# EndingsACMixOutput.net
KiCad netlist of a schematic drawn in EAGLE
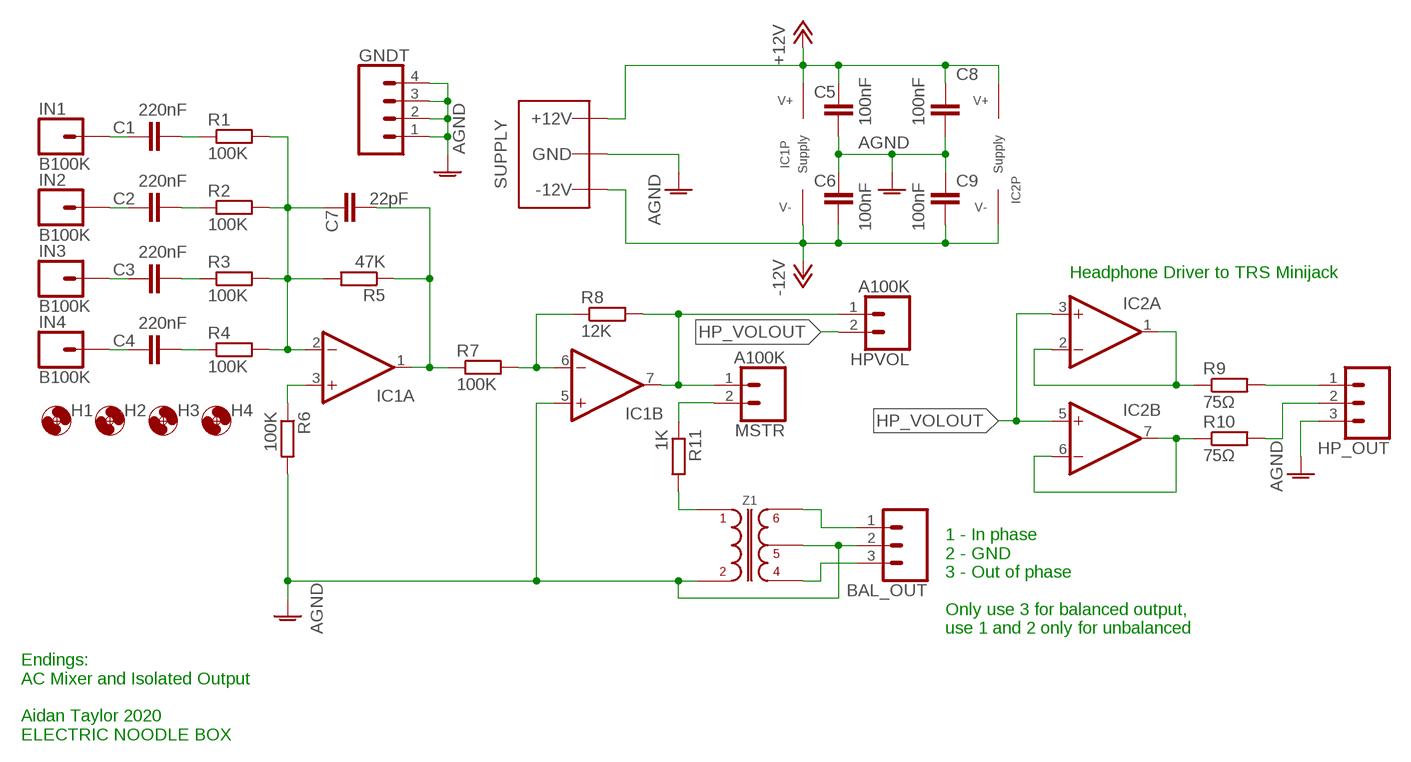
[diagram p0: schematic, sheet 1]

(export (version "E")
  (design (tool "Eeschema 10.0.6"))
  (components
    (comp (ref "BAL_OUT")
      (value "3XWIREPAD")
      (footprint "eagle-import:1X03")
      (libsource (lib "eagle-import") (part "3XWIREPAD"))
    )
    (comp (ref "C1")
      (value "220nF")
      (footprint "eagle-import:C050-025X075")
      (libsource (lib "eagle-import") (part "C-EU050-025X075"))
    )
    (comp (ref "C2")
      (value "220nF")
      (footprint "eagle-import:C050-025X075")
      (libsource (lib "eagle-import") (part "C-EU050-025X075"))
    )
    (comp (ref "C3")
      (value "220nF")
      (footprint "eagle-import:C050-025X075")
      (libsource (lib "eagle-import") (part "C-EU050-025X075"))
    )
    (comp (ref "C4")
      (value "220nF")
      (footprint "eagle-import:C050-025X075")
      (libsource (lib "eagle-import") (part "C-EU050-025X075"))
    )
    (comp (ref "C5")
      (value "100nF")
      (footprint "eagle-import:C050-025X075")
      (libsource (lib "eagle-import") (part "C-EU050-025X075"))
    )
    (comp (ref "C6")
      (value "100nF")
      (footprint "eagle-import:C050-025X075")
      (libsource (lib "eagle-import") (part "C-EU050-025X075"))
    )
    (comp (ref "C7")
      (value "22pF")
      (footprint "eagle-import:C050-025X075")
      (libsource (lib "eagle-import") (part "C-EU050-025X075"))
    )
    (comp (ref "C8")
      (value "100nF")
      (footprint "eagle-import:C050-025X075")
      (libsource (lib "eagle-import") (part "C-EU050-025X075"))
    )
    (comp (ref "C9")
      (value "100nF")
      (footprint "eagle-import:C050-025X075")
      (libsource (lib "eagle-import") (part "C-EU050-025X075"))
    )
    (comp (ref "GNDT")
      (value "4XWIREPAD")
      (footprint "eagle-import:1X04")
      (libsource (lib "eagle-import") (part "4XWIREPAD"))
    )
    (comp (ref "H1")
      (value "MOUNT-HOLE3.2")
      (footprint "eagle-import:3,2")
      (libsource (lib "eagle-import") (part "MOUNT-HOLE3.2"))
    )
    (comp (ref "H2")
      (value "MOUNT-HOLE3.2")
      (footprint "eagle-import:3,2")
      (libsource (lib "eagle-import") (part "MOUNT-HOLE3.2"))
    )
    (comp (ref "H3")
      (value "MOUNT-HOLE3.2")
      (footprint "eagle-import:3,2")
      (libsource (lib "eagle-import") (part "MOUNT-HOLE3.2"))
    )
    (comp (ref "H4")
      (value "MOUNT-HOLE3.2")
      (footprint "eagle-import:3,2")
      (libsource (lib "eagle-import") (part "MOUNT-HOLE3.2"))
    )
    (comp (ref "HPVOL")
      (value "A100K")
      (footprint "eagle-import:1X02")
      (libsource (lib "eagle-import") (part "2XWIREPAD"))
    )
    (comp (ref "HP_OUT")
      (value "3XWIREPAD")
      (footprint "eagle-import:1X03")
      (libsource (lib "eagle-import") (part "3XWIREPAD"))
    )
    (comp (ref "IC1")
      (value "TL0X2DIL")
      (footprint "eagle-import:DIL08")
      (libsource (lib "eagle-import") (part "TL0X2DIL"))
    )
    (comp (ref "IC2")
      (value "TL0X2DIL")
      (footprint "eagle-import:DIL08")
      (libsource (lib "eagle-import") (part "TL0X2DIL"))
    )
    (comp (ref "IN1")
      (value "B100K")
      (footprint "eagle-import:1X01")
      (libsource (lib "eagle-import") (part "1XWIREPAD"))
    )
    (comp (ref "IN2")
      (value "B100K")
      (footprint "eagle-import:1X01")
      (libsource (lib "eagle-import") (part "1XWIREPAD"))
    )
    (comp (ref "IN3")
      (value "B100K")
      (footprint "eagle-import:1X01")
      (libsource (lib "eagle-import") (part "1XWIREPAD"))
    )
    (comp (ref "IN4")
      (value "B100K")
      (footprint "eagle-import:1X01")
      (libsource (lib "eagle-import") (part "1XWIREPAD"))
    )
    (comp (ref "MSTR")
      (value "A100K")
      (footprint "eagle-import:1X02")
      (libsource (lib "eagle-import") (part "2XWIREPAD"))
    )
    (comp (ref "R1")
      (value "100K")
      (footprint "eagle-import:0207_10")
      (libsource (lib "eagle-import") (part "R-EU_0207/10"))
    )
    (comp (ref "R2")
      (value "100K")
      (footprint "eagle-import:0207_10")
      (libsource (lib "eagle-import") (part "R-EU_0207/10"))
    )
    (comp (ref "R3")
      (value "100K")
      (footprint "eagle-import:0207_10")
      (libsource (lib "eagle-import") (part "R-EU_0207/10"))
    )
    (comp (ref "R4")
      (value "100K")
      (footprint "eagle-import:0207_10")
      (libsource (lib "eagle-import") (part "R-EU_0207/10"))
    )
    (comp (ref "R5")
      (value "47K")
      (footprint "eagle-import:0207_10")
      (libsource (lib "eagle-import") (part "R-EU_0207/10"))
    )
    (comp (ref "R6")
      (value "100K")
      (footprint "eagle-import:0207_10")
      (libsource (lib "eagle-import") (part "R-EU_0207/10"))
    )
    (comp (ref "R7")
      (value "100K")
      (footprint "eagle-import:0207_10")
      (libsource (lib "eagle-import") (part "R-EU_0207/10"))
    )
    (comp (ref "R8")
      (value "12K")
      (footprint "eagle-import:0207_10")
      (libsource (lib "eagle-import") (part "R-EU_0207/10"))
    )
    (comp (ref "R9")
      (value "75Ω")
      (footprint "eagle-import:0207_10")
      (libsource (lib "eagle-import") (part "R-EU_0207/10"))
    )
    (comp (ref "R10")
      (value "75Ω")
      (footprint "eagle-import:0207_10")
      (libsource (lib "eagle-import") (part "R-EU_0207/10"))
    )
    (comp (ref "R11")
      (value "1K")
      (footprint "eagle-import:0207_10")
      (libsource (lib "eagle-import") (part "R-EU_0207/10"))
    )
    (comp (ref "WP1")
      (value "COMBO_SUPPLY_HEADER")
      (footprint "eagle-import:COMBINED_POWER")
      (libsource (lib "eagle-import") (part "COMBO_SUPPLY_HEADER"))
    )
    (comp (ref "Z1")
      (value "Z1604_AUDIO_TRANSFORMER")
      (footprint "eagle-import:Z1604_TRANSFORMER")
      (libsource (lib "eagle-import") (part "Z1604_AUDIO_TRANSFORMER"))
    )
  )
  (nets
    (net (code "1") (name "+12V") (class "Default")
      (node (ref "C5") (pin "1") (pinfunction "1_1") (pintype "passive"))
      (node (ref "C8") (pin "1") (pinfunction "1_1") (pintype "passive"))
      (node (ref "IC1") (pin "8") (pinfunction "V+_8") (pintype "bidirectional"))
      (node (ref "IC2") (pin "8") (pinfunction "V+_8") (pintype "bidirectional"))
      (node (ref "WP1") (pin "V+1") (pinfunction "V++_V+1") (pintype "power_in"))
      (node (ref "WP1") (pin "V+2") (pinfunction "V++_V+2") (pintype "power_in"))
      (node (ref "WP1") (pin "V+3") (pinfunction "V++_V+3") (pintype "power_in"))
    )
    (net (code "2") (name "-12V") (class "Default")
      (node (ref "C6") (pin "2") (pinfunction "2_2") (pintype "passive"))
      (node (ref "C9") (pin "2") (pinfunction "2_2") (pintype "passive"))
      (node (ref "IC1") (pin "4") (pinfunction "V-_4") (pintype "bidirectional"))
      (node (ref "IC2") (pin "4") (pinfunction "V-_4") (pintype "bidirectional"))
      (node (ref "WP1") (pin "V-1") (pinfunction "V--_V-1") (pintype "power_in"))
      (node (ref "WP1") (pin "V-2") (pinfunction "V--_V-2") (pintype "power_in"))
      (node (ref "WP1") (pin "V-3") (pinfunction "V--_V-3") (pintype "power_in"))
    )
    (net (code "3") (name "AGND") (class "Default")
      (node (ref "BAL_OUT") (pin "2") (pinfunction "2_2") (pintype "passive"))
      (node (ref "C5") (pin "2") (pinfunction "2_2") (pintype "passive"))
      (node (ref "C6") (pin "1") (pinfunction "1_1") (pintype "passive"))
      (node (ref "C8") (pin "2") (pinfunction "2_2") (pintype "passive"))
      (node (ref "C9") (pin "1") (pinfunction "1_1") (pintype "passive"))
      (node (ref "GNDT") (pin "1") (pinfunction "1_1") (pintype "passive"))
      (node (ref "GNDT") (pin "2") (pinfunction "2_2") (pintype "passive"))
      (node (ref "GNDT") (pin "3") (pinfunction "3_3") (pintype "passive"))
      (node (ref "GNDT") (pin "4") (pinfunction "4_4") (pintype "passive"))
      (node (ref "HP_OUT") (pin "3") (pinfunction "3_3") (pintype "passive"))
      (node (ref "IC1") (pin "5") (pinfunction "+IN_5") (pintype "input"))
      (node (ref "R6") (pin "2") (pinfunction "2_2") (pintype "passive"))
      (node (ref "WP1") (pin "GND1") (pinfunction "AGND_GND1") (pintype "power_in"))
      (node (ref "WP1") (pin "GND2") (pinfunction "AGND_GND2") (pintype "power_in"))
      (node (ref "WP1") (pin "GND3") (pinfunction "AGND_GND3") (pintype "power_in"))
      (node (ref "WP1") (pin "GND4") (pinfunction "AGND_GND4") (pintype "power_in"))
      (node (ref "WP1") (pin "GND5") (pinfunction "AGND_GND5") (pintype "power_in"))
      (node (ref "WP1") (pin "GND6") (pinfunction "AGND_GND6") (pintype "power_in"))
      (node (ref "WP1") (pin "GND7") (pinfunction "AGND_GND7") (pintype "power_in"))
      (node (ref "WP1") (pin "GND8") (pinfunction "AGND_GND8") (pintype "power_in"))
      (node (ref "Z1") (pin "T3") (pinfunction "3_T3") (pintype "bidirectional"))
      (node (ref "Z1") (pin "T5") (pinfunction "5_T5") (pintype "bidirectional"))
    )
    (net (code "4") (name "HP_VOLOUT") (class "Default")
      (node (ref "HPVOL") (pin "2") (pinfunction "2_2") (pintype "passive"))
      (node (ref "IC2") (pin "3") (pinfunction "+IN_3") (pintype "input"))
      (node (ref "IC2") (pin "5") (pinfunction "+IN_5") (pintype "input"))
    )
    (net (code "5") (name "Net-(C1-Pad1)") (class "Default")
      (node (ref "C1") (pin "1") (pinfunction "1_1") (pintype "passive"))
      (node (ref "IN1") (pin "1") (pinfunction "1_1") (pintype "passive"))
    )
    (net (code "6") (name "Net-(C1-Pad2)") (class "Default")
      (node (ref "C1") (pin "2") (pinfunction "2_2") (pintype "passive"))
      (node (ref "R1") (pin "1") (pinfunction "1_1") (pintype "passive"))
    )
    (net (code "7") (name "Net-(C2-Pad1)") (class "Default")
      (node (ref "C2") (pin "1") (pinfunction "1_1") (pintype "passive"))
      (node (ref "IN2") (pin "1") (pinfunction "1_1") (pintype "passive"))
    )
    (net (code "8") (name "Net-(C2-Pad2)") (class "Default")
      (node (ref "C2") (pin "2") (pinfunction "2_2") (pintype "passive"))
      (node (ref "R2") (pin "1") (pinfunction "1_1") (pintype "passive"))
    )
    (net (code "9") (name "Net-(C3-Pad1)") (class "Default")
      (node (ref "C3") (pin "1") (pinfunction "1_1") (pintype "passive"))
      (node (ref "IN3") (pin "1") (pinfunction "1_1") (pintype "passive"))
    )
    (net (code "10") (name "Net-(C3-Pad2)") (class "Default")
      (node (ref "C3") (pin "2") (pinfunction "2_2") (pintype "passive"))
      (node (ref "R3") (pin "1") (pinfunction "1_1") (pintype "passive"))
    )
    (net (code "11") (name "Net-(C4-Pad1)") (class "Default")
      (node (ref "C4") (pin "1") (pinfunction "1_1") (pintype "passive"))
      (node (ref "IN4") (pin "1") (pinfunction "1_1") (pintype "passive"))
    )
    (net (code "12") (name "Net-(C4-Pad2)") (class "Default")
      (node (ref "C4") (pin "2") (pinfunction "2_2") (pintype "passive"))
      (node (ref "R4") (pin "1") (pinfunction "1_1") (pintype "passive"))
    )
    (net (code "13") (name "Net-(HP_OUT-Pad1)") (class "Default")
      (node (ref "HP_OUT") (pin "1") (pinfunction "1_1") (pintype "passive"))
      (node (ref "R9") (pin "2") (pinfunction "2_2") (pintype "passive"))
    )
    (net (code "14") (name "Net-(HP_OUT-Pad2)") (class "Default")
      (node (ref "HP_OUT") (pin "2") (pinfunction "2_2") (pintype "passive"))
      (node (ref "R10") (pin "2") (pinfunction "2_2") (pintype "passive"))
    )
    (net (code "15") (name "Net-(IC1A-+IN)") (class "Default")
      (node (ref "IC1") (pin "3") (pinfunction "+IN_3") (pintype "input"))
      (node (ref "R6") (pin "1") (pinfunction "1_1") (pintype "passive"))
    )
    (net (code "16") (name "Net-(IC1A--IN)") (class "Default")
      (node (ref "C7") (pin "1") (pinfunction "1_1") (pintype "passive"))
      (node (ref "IC1") (pin "2") (pinfunction "-IN_2") (pintype "input"))
      (node (ref "R1") (pin "2") (pinfunction "2_2") (pintype "passive"))
      (node (ref "R2") (pin "2") (pinfunction "2_2") (pintype "passive"))
      (node (ref "R3") (pin "2") (pinfunction "2_2") (pintype "passive"))
      (node (ref "R4") (pin "2") (pinfunction "2_2") (pintype "passive"))
      (node (ref "R5") (pin "2") (pinfunction "2_2") (pintype "passive"))
    )
    (net (code "17") (name "Net-(IC1A-OUT)") (class "Default")
      (node (ref "C7") (pin "2") (pinfunction "2_2") (pintype "passive"))
      (node (ref "IC1") (pin "1") (pinfunction "OUT_1") (pintype "output"))
      (node (ref "R5") (pin "1") (pinfunction "1_1") (pintype "passive"))
      (node (ref "R7") (pin "1") (pinfunction "1_1") (pintype "passive"))
    )
    (net (code "18") (name "Net-(IC1B--IN)") (class "Default")
      (node (ref "IC1") (pin "6") (pinfunction "-IN_6") (pintype "input"))
      (node (ref "R7") (pin "2") (pinfunction "2_2") (pintype "passive"))
      (node (ref "R8") (pin "1") (pinfunction "1_1") (pintype "passive"))
    )
    (net (code "19") (name "Net-(IC1B-OUT)") (class "Default")
      (node (ref "HPVOL") (pin "1") (pinfunction "1_1") (pintype "passive"))
      (node (ref "IC1") (pin "7") (pinfunction "OUT_7") (pintype "output"))
      (node (ref "MSTR") (pin "1") (pinfunction "1_1") (pintype "passive"))
      (node (ref "R8") (pin "2") (pinfunction "2_2") (pintype "passive"))
    )
    (net (code "20") (name "Net-(IC2A--IN)") (class "Default")
      (node (ref "IC2") (pin "1") (pinfunction "OUT_1") (pintype "output"))
      (node (ref "IC2") (pin "2") (pinfunction "-IN_2") (pintype "input"))
      (node (ref "R9") (pin "1") (pinfunction "1_1") (pintype "passive"))
    )
    (net (code "21") (name "Net-(IC2B--IN)") (class "Default")
      (node (ref "IC2") (pin "6") (pinfunction "-IN_6") (pintype "input"))
      (node (ref "IC2") (pin "7") (pinfunction "OUT_7") (pintype "output"))
      (node (ref "R10") (pin "1") (pinfunction "1_1") (pintype "passive"))
    )
    (net (code "22") (name "Net-(MSTR-Pad2)") (class "Default")
      (node (ref "MSTR") (pin "2") (pinfunction "2_2") (pintype "passive"))
      (node (ref "R11") (pin "1") (pinfunction "1_1") (pintype "passive"))
    )
    (net (code "23") (name "Net-(Z1-1)") (class "Default")
      (node (ref "R11") (pin "2") (pinfunction "2_2") (pintype "passive"))
      (node (ref "Z1") (pin "T1") (pinfunction "1_T1") (pintype "bidirectional"))
    )
    (net (code "24") (name "Net-(Z1-4)") (class "Default")
      (node (ref "BAL_OUT") (pin "3") (pinfunction "3_3") (pintype "passive"))
      (node (ref "Z1") (pin "T4") (pinfunction "4_T4") (pintype "bidirectional"))
    )
    (net (code "25") (name "Net-(Z1-6)") (class "Default")
      (node (ref "BAL_OUT") (pin "1") (pinfunction "1_1") (pintype "passive"))
      (node (ref "Z1") (pin "T6") (pinfunction "6_T6") (pintype "bidirectional"))
    )
  )
)
